# main.net
KiCad netlist of a schematic drawn in Altium Designer
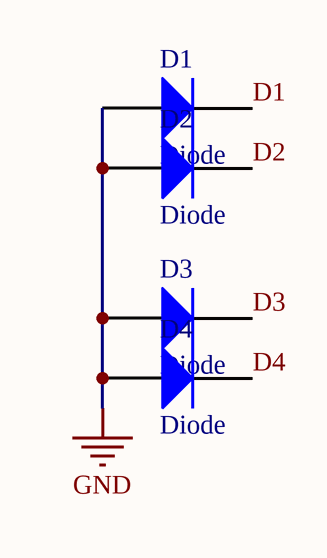
[diagram p0: main.SchDoc]

(export (version "E")
  (design (tool "Eeschema 10.0.6"))
  (components
    (comp (ref "D1")
      (value "Diode")
      (footprint "PIN-diode")
      (description "Default Diode")
      (fields (field (name "PUBLISHER") "Altium Limited"))
      (libsource (lib "Miscellaneous Devices") (part "Diode"))
    )
    (comp (ref "D2")
      (value "Diode")
      (footprint "PIN-diode")
      (description "Default Diode")
      (fields (field (name "PUBLISHER") "Altium Limited"))
      (libsource (lib "Miscellaneous Devices") (part "Diode"))
    )
    (comp (ref "D3")
      (value "Diode")
      (footprint "PIN-diode")
      (description "Default Diode")
      (fields (field (name "PUBLISHER") "Altium Limited"))
      (libsource (lib "Miscellaneous Devices") (part "Diode"))
    )
    (comp (ref "D4")
      (value "Diode")
      (footprint "PIN-diode")
      (description "Default Diode")
      (fields (field (name "PUBLISHER") "Altium Limited"))
      (libsource (lib "Miscellaneous Devices") (part "Diode"))
    )
  )
  (nets
    (net (code "1") (name "/D1") (class "Default")
      (node (ref "D1") (pin "2") (pinfunction "K_2") (pintype "passive"))
    )
    (net (code "2") (name "/D2") (class "Default")
      (node (ref "D2") (pin "2") (pinfunction "K_2") (pintype "passive"))
    )
    (net (code "3") (name "/D3") (class "Default")
      (node (ref "D3") (pin "2") (pinfunction "K_2") (pintype "passive"))
    )
    (net (code "4") (name "/D4") (class "Default")
      (node (ref "D4") (pin "2") (pinfunction "K_2") (pintype "passive"))
    )
    (net (code "5") (name "GND") (class "Default")
      (node (ref "D1") (pin "1") (pinfunction "A_1") (pintype "passive"))
      (node (ref "D2") (pin "1") (pinfunction "A_1") (pintype "passive"))
      (node (ref "D3") (pin "1") (pinfunction "A_1") (pintype "passive"))
      (node (ref "D4") (pin "1") (pinfunction "A_1") (pintype "passive"))
    )
  )
)
